# arduino_wireless_shield_rev_1_0.net
KiCad netlist of a schematic drawn in EAGLE
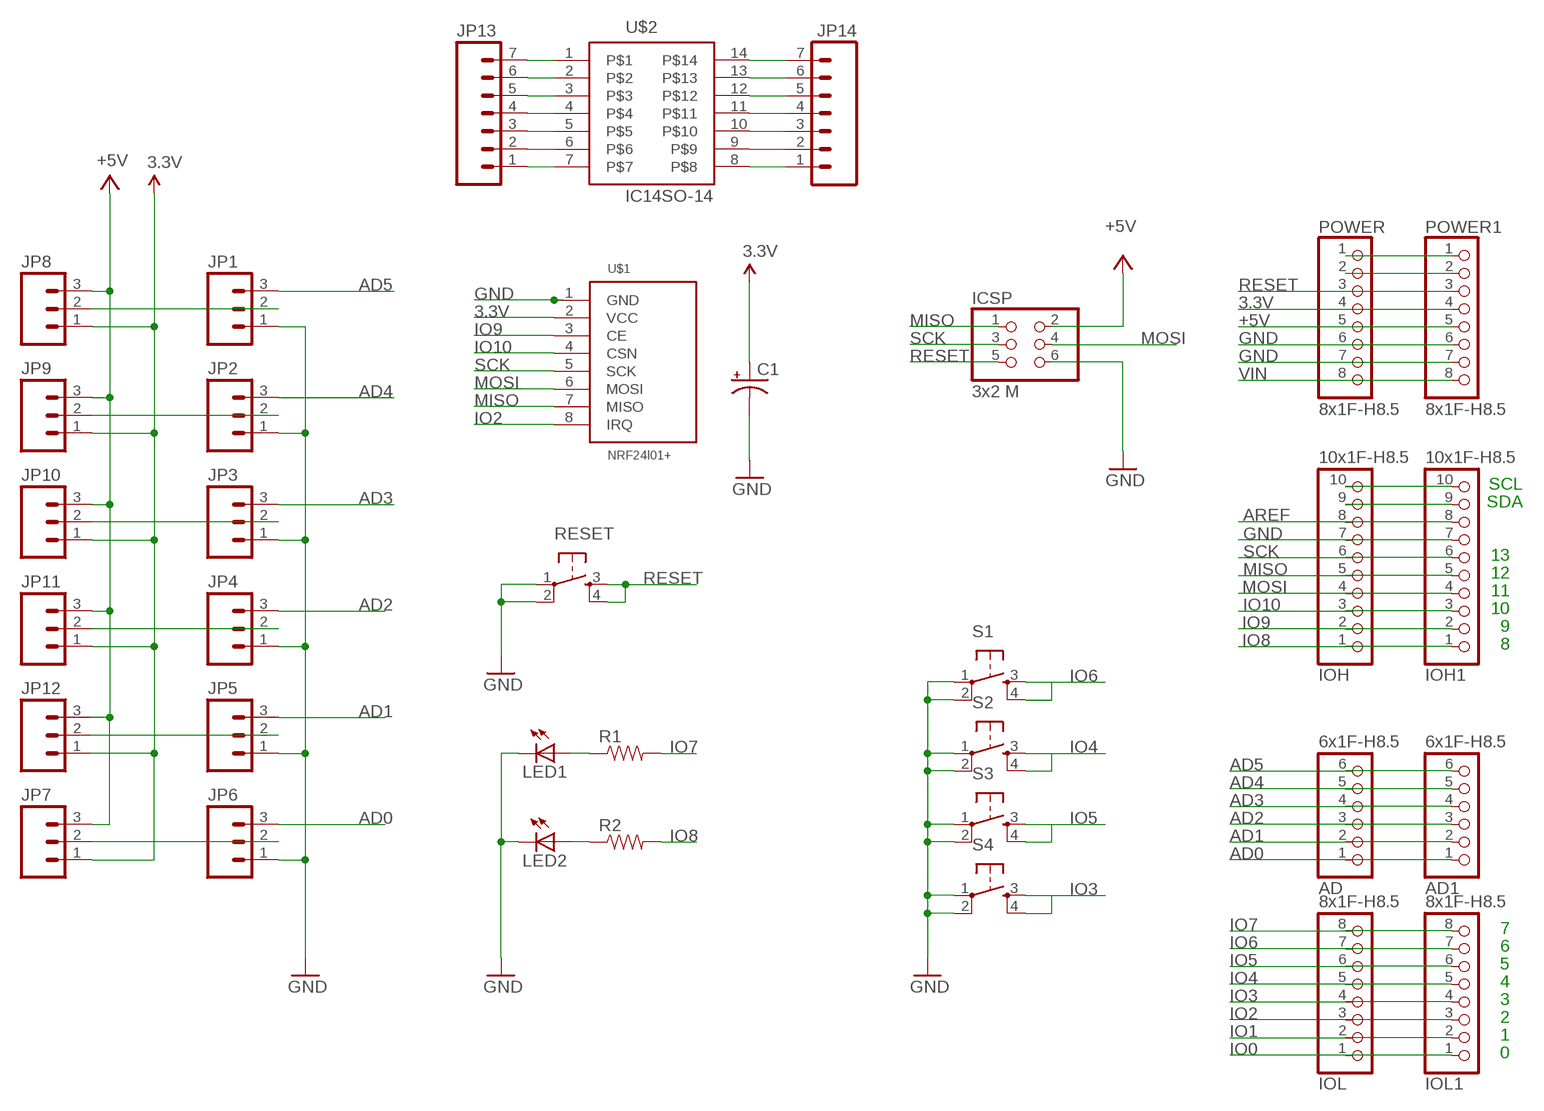
[diagram p0: schematic, sheet 1]

(export (version "E")
  (design (tool "Eeschema 10.0.6"))
  (components
    (comp (ref "AD")
      (value "6x1F-H8.5")
      (footprint "eagle-import:1X06")
      (libsource (lib "eagle-import") (part "PINHD-1X6"))
    )
    (comp (ref "AD1")
      (value "6x1F-H8.5")
      (footprint "eagle-import:1X06")
      (libsource (lib "eagle-import") (part "PINHD-1X6"))
    )
    (comp (ref "C1")
      (value "CPOL-USTT2D7")
      (footprint "eagle-import:TT2D7")
      (libsource (lib "eagle-import") (part "CPOL-USTT2D7"))
    )
    (comp (ref "ICSP")
      (value "3x2 M")
      (footprint "eagle-import:2X03")
      (libsource (lib "eagle-import") (part "PINHD-2X3"))
    )
    (comp (ref "IOH")
      (value "10x1F-H8.5")
      (footprint "eagle-import:1X10")
      (libsource (lib "eagle-import") (part "PINHD-1X10_ARD"))
    )
    (comp (ref "IOH1")
      (value "10x1F-H8.5")
      (footprint "eagle-import:1X10")
      (libsource (lib "eagle-import") (part "PINHD-1X10_ARD"))
    )
    (comp (ref "IOL")
      (value "8x1F-H8.5")
      (footprint "eagle-import:1X08")
      (libsource (lib "eagle-import") (part "PINHD-1X8"))
    )
    (comp (ref "IOL1")
      (value "8x1F-H8.5")
      (footprint "eagle-import:1X08")
      (libsource (lib "eagle-import") (part "PINHD-1X8"))
    )
    (comp (ref "JP1")
      (value "M03PTH")
      (footprint "eagle-import:1X03")
      (libsource (lib "eagle-import") (part "M03PTH"))
    )
    (comp (ref "JP2")
      (value "M03PTH")
      (footprint "eagle-import:1X03")
      (libsource (lib "eagle-import") (part "M03PTH"))
    )
    (comp (ref "JP3")
      (value "M03PTH")
      (footprint "eagle-import:1X03")
      (libsource (lib "eagle-import") (part "M03PTH"))
    )
    (comp (ref "JP4")
      (value "M03PTH")
      (footprint "eagle-import:1X03")
      (libsource (lib "eagle-import") (part "M03PTH"))
    )
    (comp (ref "JP5")
      (value "M03PTH")
      (footprint "eagle-import:1X03")
      (libsource (lib "eagle-import") (part "M03PTH"))
    )
    (comp (ref "JP6")
      (value "M03PTH")
      (footprint "eagle-import:1X03")
      (libsource (lib "eagle-import") (part "M03PTH"))
    )
    (comp (ref "JP7")
      (value "M03PTH")
      (footprint "eagle-import:1X03")
      (libsource (lib "eagle-import") (part "M03PTH"))
    )
    (comp (ref "JP8")
      (value "M03PTH")
      (footprint "eagle-import:1X03")
      (libsource (lib "eagle-import") (part "M03PTH"))
    )
    (comp (ref "JP9")
      (value "M03PTH")
      (footprint "eagle-import:1X03")
      (libsource (lib "eagle-import") (part "M03PTH"))
    )
    (comp (ref "JP10")
      (value "M03PTH")
      (footprint "eagle-import:1X03")
      (libsource (lib "eagle-import") (part "M03PTH"))
    )
    (comp (ref "JP11")
      (value "M03PTH")
      (footprint "eagle-import:1X03")
      (libsource (lib "eagle-import") (part "M03PTH"))
    )
    (comp (ref "JP12")
      (value "M03PTH")
      (footprint "eagle-import:1X03")
      (libsource (lib "eagle-import") (part "M03PTH"))
    )
    (comp (ref "JP13")
      (value "M07")
      (footprint "eagle-import:1X07")
      (libsource (lib "eagle-import") (part "M07"))
    )
    (comp (ref "JP14")
      (value "M07")
      (footprint "eagle-import:1X07")
      (libsource (lib "eagle-import") (part "M07"))
    )
    (comp (ref "LED1")
      (value "LED5MM")
      (footprint "eagle-import:LED5MM")
      (libsource (lib "eagle-import") (part "LED5MM"))
    )
    (comp (ref "LED2")
      (value "LED5MM")
      (footprint "eagle-import:LED5MM")
      (libsource (lib "eagle-import") (part "LED5MM"))
    )
    (comp (ref "POWER")
      (value "8x1F-H8.5")
      (footprint "eagle-import:1X08")
      (libsource (lib "eagle-import") (part "PINHD-1X8"))
    )
    (comp (ref "POWER1")
      (value "8x1F-H8.5")
      (footprint "eagle-import:1X08")
      (libsource (lib "eagle-import") (part "PINHD-1X8"))
    )
    (comp (ref "R1")
      (value "RESISTORPTH-1/4W")
      (footprint "eagle-import:AXIAL-0.4")
      (libsource (lib "eagle-import") (part "RESISTORPTH-1/4W"))
    )
    (comp (ref "R2")
      (value "RESISTORPTH-1/4W")
      (footprint "eagle-import:AXIAL-0.4")
      (libsource (lib "eagle-import") (part "RESISTORPTH-1/4W"))
    )
    (comp (ref "RESET")
      (value "TAC_SWITCHPTH")
      (footprint "eagle-import:TACTILE-PTH")
      (libsource (lib "eagle-import") (part "TAC_SWITCHPTH"))
    )
    (comp (ref "S1")
      (value "TAC_SWITCHPTH")
      (footprint "eagle-import:TACTILE-PTH")
      (libsource (lib "eagle-import") (part "TAC_SWITCHPTH"))
    )
    (comp (ref "S2")
      (value "TAC_SWITCHPTH")
      (footprint "eagle-import:TACTILE-PTH")
      (libsource (lib "eagle-import") (part "TAC_SWITCHPTH"))
    )
    (comp (ref "S3")
      (value "TAC_SWITCHPTH")
      (footprint "eagle-import:TACTILE-PTH")
      (libsource (lib "eagle-import") (part "TAC_SWITCHPTH"))
    )
    (comp (ref "S4")
      (value "TAC_SWITCHPTH")
      (footprint "eagle-import:TACTILE-PTH")
      (libsource (lib "eagle-import") (part "TAC_SWITCHPTH"))
    )
    (comp (ref "U$1")
      (value "NRF24L01+_MODULE")
      (footprint "eagle-import:NRF24L01+MODULE")
      (libsource (lib "eagle-import") (part "NRF24L01+_MODULE"))
    )
    (comp (ref "U$2")
      (value "IC14SO-14")
      (footprint "eagle-import:SO14")
      (libsource (lib "eagle-import") (part "IC14SO-14"))
    )
  )
  (nets
    (net (code "1") (name "+5V") (class "Default")
      (node (ref "ICSP") (pin "2") (pinfunction "2_2") (pintype "passive"))
      (node (ref "JP10") (pin "3") (pinfunction "3_3") (pintype "passive"))
      (node (ref "JP11") (pin "3") (pinfunction "3_3") (pintype "passive"))
      (node (ref "JP12") (pin "3") (pinfunction "3_3") (pintype "passive"))
      (node (ref "JP7") (pin "3") (pinfunction "3_3") (pintype "passive"))
      (node (ref "JP8") (pin "3") (pinfunction "3_3") (pintype "passive"))
      (node (ref "JP9") (pin "3") (pinfunction "3_3") (pintype "passive"))
      (node (ref "POWER") (pin "5") (pinfunction "5_5") (pintype "passive"))
      (node (ref "POWER1") (pin "5") (pinfunction "5_5") (pintype "passive"))
    )
    (net (code "2") (name "/AD0") (class "Default")
      (node (ref "AD") (pin "1") (pinfunction "1_1") (pintype "passive"))
      (node (ref "AD1") (pin "1") (pinfunction "1_1") (pintype "passive"))
      (node (ref "JP6") (pin "3") (pinfunction "3_3") (pintype "passive"))
    )
    (net (code "3") (name "/AD1") (class "Default")
      (node (ref "AD") (pin "2") (pinfunction "2_2") (pintype "passive"))
      (node (ref "AD1") (pin "2") (pinfunction "2_2") (pintype "passive"))
      (node (ref "JP5") (pin "3") (pinfunction "3_3") (pintype "passive"))
    )
    (net (code "4") (name "/AD2") (class "Default")
      (node (ref "AD") (pin "3") (pinfunction "3_3") (pintype "passive"))
      (node (ref "AD1") (pin "3") (pinfunction "3_3") (pintype "passive"))
      (node (ref "JP4") (pin "3") (pinfunction "3_3") (pintype "passive"))
    )
    (net (code "5") (name "/AD3") (class "Default")
      (node (ref "AD") (pin "4") (pinfunction "4_4") (pintype "passive"))
      (node (ref "AD1") (pin "4") (pinfunction "4_4") (pintype "passive"))
      (node (ref "JP3") (pin "3") (pinfunction "3_3") (pintype "passive"))
    )
    (net (code "6") (name "/AD4") (class "Default")
      (node (ref "AD") (pin "5") (pinfunction "5_5") (pintype "passive"))
      (node (ref "AD1") (pin "5") (pinfunction "5_5") (pintype "passive"))
      (node (ref "JP2") (pin "3") (pinfunction "3_3") (pintype "passive"))
    )
    (net (code "7") (name "/AD5") (class "Default")
      (node (ref "AD") (pin "6") (pinfunction "6_6") (pintype "passive"))
      (node (ref "AD1") (pin "6") (pinfunction "6_6") (pintype "passive"))
      (node (ref "JP1") (pin "3") (pinfunction "3_3") (pintype "passive"))
    )
    (net (code "8") (name "/AREF") (class "Default")
      (node (ref "IOH") (pin "8") (pinfunction "8_8") (pintype "passive"))
      (node (ref "IOH1") (pin "8") (pinfunction "8_8") (pintype "passive"))
    )
    (net (code "9") (name "/IO0") (class "Default")
      (node (ref "IOL") (pin "1") (pinfunction "1_1") (pintype "passive"))
      (node (ref "IOL1") (pin "1") (pinfunction "1_1") (pintype "passive"))
    )
    (net (code "10") (name "/IO1") (class "Default")
      (node (ref "IOL") (pin "2") (pinfunction "2_2") (pintype "passive"))
      (node (ref "IOL1") (pin "2") (pinfunction "2_2") (pintype "passive"))
    )
    (net (code "11") (name "/IO2") (class "Default")
      (node (ref "IOL") (pin "3") (pinfunction "3_3") (pintype "passive"))
      (node (ref "IOL1") (pin "3") (pinfunction "3_3") (pintype "passive"))
      (node (ref "U$1") (pin "8") (pinfunction "IRQ_8") (pintype "output"))
    )
    (net (code "12") (name "/IO3") (class "Default")
      (node (ref "IOL") (pin "4") (pinfunction "4_4") (pintype "passive"))
      (node (ref "IOL1") (pin "4") (pinfunction "4_4") (pintype "passive"))
      (node (ref "S4") (pin "3") (pinfunction "3_3") (pintype "passive"))
      (node (ref "S4") (pin "4") (pinfunction "4_4") (pintype "passive"))
    )
    (net (code "13") (name "/IO4") (class "Default")
      (node (ref "IOL") (pin "5") (pinfunction "5_5") (pintype "passive"))
      (node (ref "IOL1") (pin "5") (pinfunction "5_5") (pintype "passive"))
      (node (ref "S2") (pin "3") (pinfunction "3_3") (pintype "passive"))
      (node (ref "S2") (pin "4") (pinfunction "4_4") (pintype "passive"))
    )
    (net (code "14") (name "/IO5") (class "Default")
      (node (ref "IOL") (pin "6") (pinfunction "6_6") (pintype "passive"))
      (node (ref "IOL1") (pin "6") (pinfunction "6_6") (pintype "passive"))
      (node (ref "S3") (pin "3") (pinfunction "3_3") (pintype "passive"))
      (node (ref "S3") (pin "4") (pinfunction "4_4") (pintype "passive"))
    )
    (net (code "15") (name "/IO6") (class "Default")
      (node (ref "IOL") (pin "7") (pinfunction "7_7") (pintype "passive"))
      (node (ref "IOL1") (pin "7") (pinfunction "7_7") (pintype "passive"))
      (node (ref "S1") (pin "3") (pinfunction "3_3") (pintype "passive"))
      (node (ref "S1") (pin "4") (pinfunction "4_4") (pintype "passive"))
    )
    (net (code "16") (name "/IO7") (class "Default")
      (node (ref "IOL") (pin "8") (pinfunction "8_8") (pintype "passive"))
      (node (ref "IOL1") (pin "8") (pinfunction "8_8") (pintype "passive"))
      (node (ref "R1") (pin "P$2") (pinfunction "2_P$2") (pintype "passive"))
    )
    (net (code "17") (name "/IO8") (class "Default")
      (node (ref "IOH") (pin "1") (pinfunction "1_1") (pintype "passive"))
      (node (ref "IOH1") (pin "1") (pinfunction "1_1") (pintype "passive"))
      (node (ref "R2") (pin "P$2") (pinfunction "2_P$2") (pintype "passive"))
    )
    (net (code "18") (name "/IO9") (class "Default")
      (node (ref "IOH") (pin "2") (pinfunction "2_2") (pintype "passive"))
      (node (ref "IOH1") (pin "2") (pinfunction "2_2") (pintype "passive"))
      (node (ref "U$1") (pin "3") (pinfunction "CE_3") (pintype "input"))
    )
    (net (code "19") (name "/IO10") (class "Default")
      (node (ref "IOH") (pin "3") (pinfunction "3_3") (pintype "passive"))
      (node (ref "IOH1") (pin "3") (pinfunction "3_3") (pintype "passive"))
      (node (ref "U$1") (pin "4") (pinfunction "CSN_4") (pintype "input"))
    )
    (net (code "20") (name "/MISO") (class "Default")
      (node (ref "ICSP") (pin "1") (pinfunction "1_1") (pintype "passive"))
      (node (ref "IOH") (pin "5") (pinfunction "5_5") (pintype "passive"))
      (node (ref "IOH1") (pin "5") (pinfunction "5_5") (pintype "passive"))
      (node (ref "U$1") (pin "7") (pinfunction "MISO_7") (pintype "output"))
    )
    (net (code "21") (name "/MOSI") (class "Default")
      (node (ref "ICSP") (pin "4") (pinfunction "4_4") (pintype "passive"))
      (node (ref "IOH") (pin "4") (pinfunction "4_4") (pintype "passive"))
      (node (ref "IOH1") (pin "4") (pinfunction "4_4") (pintype "passive"))
      (node (ref "U$1") (pin "6") (pinfunction "MOSI_6") (pintype "input"))
    )
    (net (code "22") (name "/RESET") (class "Default")
      (node (ref "ICSP") (pin "5") (pinfunction "5_5") (pintype "passive"))
      (node (ref "POWER") (pin "3") (pinfunction "3_3") (pintype "passive"))
      (node (ref "POWER1") (pin "3") (pinfunction "3_3") (pintype "passive"))
      (node (ref "RESET") (pin "3") (pinfunction "3_3") (pintype "passive"))
      (node (ref "RESET") (pin "4") (pinfunction "4_4") (pintype "passive"))
    )
    (net (code "23") (name "/SCK") (class "Default")
      (node (ref "ICSP") (pin "3") (pinfunction "3_3") (pintype "passive"))
      (node (ref "IOH") (pin "6") (pinfunction "6_6") (pintype "passive"))
      (node (ref "IOH1") (pin "6") (pinfunction "6_6") (pintype "passive"))
      (node (ref "U$1") (pin "5") (pinfunction "SCK_5") (pintype "input"))
    )
    (net (code "24") (name "/VIN") (class "Default")
      (node (ref "POWER") (pin "8") (pinfunction "8_8") (pintype "passive"))
      (node (ref "POWER1") (pin "8") (pinfunction "8_8") (pintype "passive"))
    )
    (net (code "25") (name "3.3V") (class "Default")
      (node (ref "C1") (pin "+") (pinfunction "+_+") (pintype "passive"))
      (node (ref "JP10") (pin "1") (pinfunction "1_1") (pintype "passive"))
      (node (ref "JP11") (pin "1") (pinfunction "1_1") (pintype "passive"))
      (node (ref "JP12") (pin "1") (pinfunction "1_1") (pintype "passive"))
      (node (ref "JP7") (pin "1") (pinfunction "1_1") (pintype "passive"))
      (node (ref "JP8") (pin "1") (pinfunction "1_1") (pintype "passive"))
      (node (ref "JP9") (pin "1") (pinfunction "1_1") (pintype "passive"))
      (node (ref "POWER") (pin "4") (pinfunction "4_4") (pintype "passive"))
      (node (ref "POWER1") (pin "4") (pinfunction "4_4") (pintype "passive"))
      (node (ref "U$1") (pin "2") (pinfunction "VCC_2") (pintype "power_in"))
    )
    (net (code "26") (name "GND") (class "Default")
      (node (ref "C1") (pin "-") (pinfunction "-_-") (pintype "passive"))
      (node (ref "ICSP") (pin "6") (pinfunction "6_6") (pintype "passive"))
      (node (ref "IOH") (pin "7") (pinfunction "7_7") (pintype "passive"))
      (node (ref "IOH1") (pin "7") (pinfunction "7_7") (pintype "passive"))
      (node (ref "JP1") (pin "1") (pinfunction "1_1") (pintype "passive"))
      (node (ref "JP2") (pin "1") (pinfunction "1_1") (pintype "passive"))
      (node (ref "JP3") (pin "1") (pinfunction "1_1") (pintype "passive"))
      (node (ref "JP4") (pin "1") (pinfunction "1_1") (pintype "passive"))
      (node (ref "JP5") (pin "1") (pinfunction "1_1") (pintype "passive"))
      (node (ref "JP6") (pin "1") (pinfunction "1_1") (pintype "passive"))
      (node (ref "LED1") (pin "K") (pinfunction "C_K") (pintype "passive"))
      (node (ref "LED2") (pin "K") (pinfunction "C_K") (pintype "passive"))
      (node (ref "POWER") (pin "6") (pinfunction "6_6") (pintype "passive"))
      (node (ref "POWER") (pin "7") (pinfunction "7_7") (pintype "passive"))
      (node (ref "POWER1") (pin "6") (pinfunction "6_6") (pintype "passive"))
      (node (ref "POWER1") (pin "7") (pinfunction "7_7") (pintype "passive"))
      (node (ref "RESET") (pin "1") (pinfunction "1_1") (pintype "passive"))
      (node (ref "RESET") (pin "2") (pinfunction "2_2") (pintype "passive"))
      (node (ref "S1") (pin "1") (pinfunction "1_1") (pintype "passive"))
      (node (ref "S1") (pin "2") (pinfunction "2_2") (pintype "passive"))
      (node (ref "S2") (pin "1") (pinfunction "1_1") (pintype "passive"))
      (node (ref "S2") (pin "2") (pinfunction "2_2") (pintype "passive"))
      (node (ref "S3") (pin "1") (pinfunction "1_1") (pintype "passive"))
      (node (ref "S3") (pin "2") (pinfunction "2_2") (pintype "passive"))
      (node (ref "S4") (pin "1") (pinfunction "1_1") (pintype "passive"))
      (node (ref "S4") (pin "2") (pinfunction "2_2") (pintype "passive"))
      (node (ref "U$1") (pin "1") (pinfunction "GND_1") (pintype "power_in"))
    )
    (net (code "27") (name "Net-(IOH-Pad9)") (class "Default")
      (node (ref "IOH") (pin "9") (pinfunction "9_9") (pintype "passive"))
      (node (ref "IOH1") (pin "9") (pinfunction "9_9") (pintype "passive"))
    )
    (net (code "28") (name "Net-(IOH-Pad10)") (class "Default")
      (node (ref "IOH") (pin "10") (pinfunction "10_10") (pintype "passive"))
      (node (ref "IOH1") (pin "10") (pinfunction "10_10") (pintype "passive"))
    )
    (net (code "29") (name "Net-(JP1-Pad2)") (class "Default")
      (node (ref "JP1") (pin "2") (pinfunction "2_2") (pintype "passive"))
      (node (ref "JP8") (pin "2") (pinfunction "2_2") (pintype "passive"))
    )
    (net (code "30") (name "Net-(JP2-Pad2)") (class "Default")
      (node (ref "JP2") (pin "2") (pinfunction "2_2") (pintype "passive"))
      (node (ref "JP9") (pin "2") (pinfunction "2_2") (pintype "passive"))
    )
    (net (code "31") (name "Net-(JP6-Pad2)") (class "Default")
      (node (ref "JP6") (pin "2") (pinfunction "2_2") (pintype "passive"))
      (node (ref "JP7") (pin "2") (pinfunction "2_2") (pintype "passive"))
    )
    (net (code "32") (name "Net-(JP10-Pad2)") (class "Default")
      (node (ref "JP10") (pin "2") (pinfunction "2_2") (pintype "passive"))
      (node (ref "JP3") (pin "2") (pinfunction "2_2") (pintype "passive"))
    )
    (net (code "33") (name "Net-(JP11-Pad2)") (class "Default")
      (node (ref "JP11") (pin "2") (pinfunction "2_2") (pintype "passive"))
      (node (ref "JP4") (pin "2") (pinfunction "2_2") (pintype "passive"))
    )
    (net (code "34") (name "Net-(JP12-Pad2)") (class "Default")
      (node (ref "JP12") (pin "2") (pinfunction "2_2") (pintype "passive"))
      (node (ref "JP5") (pin "2") (pinfunction "2_2") (pintype "passive"))
    )
    (net (code "35") (name "Net-(POWER-Pad1)") (class "Default")
      (node (ref "POWER") (pin "1") (pinfunction "1_1") (pintype "passive"))
      (node (ref "POWER1") (pin "1") (pinfunction "1_1") (pintype "passive"))
    )
    (net (code "36") (name "Net-(POWER-Pad2)") (class "Default")
      (node (ref "POWER") (pin "2") (pinfunction "2_2") (pintype "passive"))
      (node (ref "POWER1") (pin "2") (pinfunction "2_2") (pintype "passive"))
    )
    (net (code "37") (name "Net-(R1-1)") (class "Default")
      (node (ref "LED1") (pin "A") (pinfunction "A_A") (pintype "passive"))
      (node (ref "R1") (pin "P$1") (pinfunction "1_P$1") (pintype "passive"))
    )
    (net (code "38") (name "Net-(R2-1)") (class "Default")
      (node (ref "LED2") (pin "A") (pinfunction "A_A") (pintype "passive"))
      (node (ref "R2") (pin "P$1") (pinfunction "1_P$1") (pintype "passive"))
    )
    (net (code "39") (name "Net-(U$2-P$1)") (class "Default")
      (node (ref "JP13") (pin "7") (pinfunction "7_7") (pintype "passive"))
      (node (ref "U$2") (pin "1") (pinfunction "P$1_1") (pintype "bidirectional"))
    )
    (net (code "40") (name "Net-(U$2-P$2)") (class "Default")
      (node (ref "JP13") (pin "6") (pinfunction "6_6") (pintype "passive"))
      (node (ref "U$2") (pin "2") (pinfunction "P$2_2") (pintype "bidirectional"))
    )
    (net (code "41") (name "Net-(U$2-P$3)") (class "Default")
      (node (ref "JP13") (pin "5") (pinfunction "5_5") (pintype "passive"))
      (node (ref "U$2") (pin "3") (pinfunction "P$3_3") (pintype "bidirectional"))
    )
    (net (code "42") (name "Net-(U$2-P$4)") (class "Default")
      (node (ref "JP13") (pin "4") (pinfunction "4_4") (pintype "passive"))
      (node (ref "U$2") (pin "4") (pinfunction "P$4_4") (pintype "bidirectional"))
    )
    (net (code "43") (name "Net-(U$2-P$5)") (class "Default")
      (node (ref "JP13") (pin "3") (pinfunction "3_3") (pintype "passive"))
      (node (ref "U$2") (pin "5") (pinfunction "P$5_5") (pintype "bidirectional"))
    )
    (net (code "44") (name "Net-(U$2-P$6)") (class "Default")
      (node (ref "JP13") (pin "2") (pinfunction "2_2") (pintype "passive"))
      (node (ref "U$2") (pin "6") (pinfunction "P$6_6") (pintype "bidirectional"))
    )
    (net (code "45") (name "Net-(U$2-P$7)") (class "Default")
      (node (ref "JP13") (pin "1") (pinfunction "1_1") (pintype "passive"))
      (node (ref "U$2") (pin "7") (pinfunction "P$7_7") (pintype "bidirectional"))
    )
    (net (code "46") (name "Net-(U$2-P$8)") (class "Default")
      (node (ref "JP14") (pin "1") (pinfunction "1_1") (pintype "passive"))
      (node (ref "U$2") (pin "8") (pinfunction "P$8_8") (pintype "bidirectional"))
    )
    (net (code "47") (name "Net-(U$2-P$9)") (class "Default")
      (node (ref "JP14") (pin "2") (pinfunction "2_2") (pintype "passive"))
      (node (ref "U$2") (pin "9") (pinfunction "P$9_9") (pintype "bidirectional"))
    )
    (net (code "48") (name "Net-(U$2-P$10)") (class "Default")
      (node (ref "JP14") (pin "3") (pinfunction "3_3") (pintype "passive"))
      (node (ref "U$2") (pin "10") (pinfunction "P$10_10") (pintype "bidirectional"))
    )
    (net (code "49") (name "Net-(U$2-P$11)") (class "Default")
      (node (ref "JP14") (pin "4") (pinfunction "4_4") (pintype "passive"))
      (node (ref "U$2") (pin "11") (pinfunction "P$11_11") (pintype "bidirectional"))
    )
    (net (code "50") (name "Net-(U$2-P$12)") (class "Default")
      (node (ref "JP14") (pin "5") (pinfunction "5_5") (pintype "passive"))
      (node (ref "U$2") (pin "12") (pinfunction "P$12_12") (pintype "bidirectional"))
    )
    (net (code "51") (name "Net-(U$2-P$13)") (class "Default")
      (node (ref "JP14") (pin "6") (pinfunction "6_6") (pintype "passive"))
      (node (ref "U$2") (pin "13") (pinfunction "P$13_13") (pintype "bidirectional"))
    )
    (net (code "52") (name "Net-(U$2-P$14)") (class "Default")
      (node (ref "JP14") (pin "7") (pinfunction "7_7") (pintype "passive"))
      (node (ref "U$2") (pin "14") (pinfunction "P$14_14") (pintype "bidirectional"))
    )
  )
)
